# 24_to_33V__for_Ionizer_Chips.net
KiCad netlist of a schematic drawn in Altium Designer
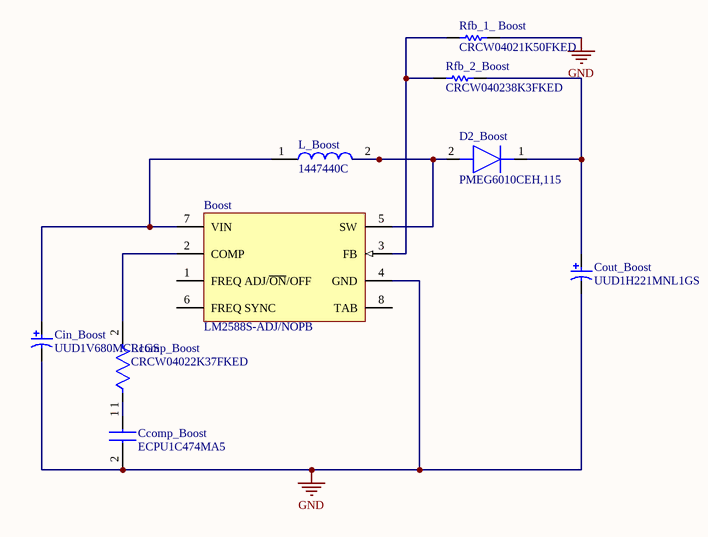
[diagram p0: 24_to_33V_(for_Ionizer_Chips).SchDoc]

(export (version "E")
  (design (tool "Eeschema 10.0.6"))
  (components
    (comp (ref "Boost")
      (value "LM2588S-ADJ/NOPB")
      (footprint "KTW0007B_N")
      (description "SIMPLE SWITCHER® 5A Flyback Regulator with Shutdown, 7-pin TO-263, Pb-Free")
      (fields (field (name "MANUFACTURER") "Texas Instruments"))
      (libsource (lib "Altium Content Vault") (part "PM-SWREG-LM2586S-12"))
    )
    (comp (ref "Ccomp_Boost")
      (value "ECPU1C474MA5")
      (footprint "SamacSys:ECPU1C154MA5")
      (description "Capacitor")
      (libsource (lib "*") (part "ECPU1C474MA5"))
    )
    (comp (ref "Cin_Boost")
      (value "UUD1V680MCL1GS")
      (footprint "NIC-CAPA2-6.3X7.7_V")
      (fields (field (name "MANUFACTURER") "Nichicon"))
      (libsource (lib "Altium Content Vault") (part "NIC-CAP-P-2"))
    )
    (comp (ref "Cout_Boost")
      (value "UUD1H221MNL1GS")
      (footprint "NIC-CAPA2-10X10_V")
      (fields (field (name "MANUFACTURER") "Nichicon"))
      (libsource (lib "Altium Content Vault") (part "NIC-CAP-P-2"))
    )
    (comp (ref "D2_Boost")
      (value "PMEG6010CEH,115")
      (footprint "SamacSys:SODFL3516X120N")
      (description "Diode")
      (fields (field (name "MOUSER PART NUMBER") "771-PMEG6010CEH-T/R"))
      (libsource (lib "*") (part "PMEG6010CEH,115"))
    )
    (comp (ref "L_Boost")
      (value "1447440C")
      (footprint "SamacSys:1447440C")
      (description "Inductor")
      (fields (field (name "MOUSER PART NUMBER") "580-1447440C"))
      (libsource (lib "*") (part "1447440C"))
    )
    (comp (ref "Rcomp_Boost")
      (value "CRCW04022K37FKED")
      (footprint "FP-CRCW0402-e3-IPC_B")
      (description "RES Thick Film, 2.37kΩ, 1%, 0.063W, 100ppm/°C, 0402")
      (fields (field (name "TOLERANCE") "1%"))
      (libsource (lib "Altium Content Vault") (part "1029c3af85768c4190bb7ad29bc67b5"))
    )
    (comp (ref "Rfb_1_ Boost")
      (value "CRCW04021K50FKED")
      (footprint "RESC1005X40X25NL05T05")
      (fields (field (name "MANUFACTURER") "Vishay Dale"))
      (libsource (lib "Altium Content Vault") (part "RES"))
    )
    (comp (ref "Rfb_2_Boost")
      (value "CRCW040238K3FKED")
      (footprint "RESC1005X40X25NL05T05")
      (fields (field (name "MANUFACTURER") "Vishay Dale"))
      (libsource (lib "Altium Content Vault") (part "RES"))
    )
  )
  (nets
    (net (code "1") (name "GND") (class "Default")
      (node (ref "Boost") (pin "4") (pinfunction "GND_4") (pintype "power_in"))
      (node (ref "Ccomp_Boost") (pin "2") (pinfunction "2_2") (pintype "passive"))
      (node (ref "Cin_Boost") (pin "2") (pinfunction "2_2") (pintype "passive"))
      (node (ref "Cout_Boost") (pin "2") (pinfunction "2_2") (pintype "passive"))
      (node (ref "Rfb_1_ Boost") (pin "2") (pinfunction "2_2") (pintype "passive"))
    )
    (net (code "2") (name "Net-(Boost-COMP)") (class "Default")
      (node (ref "Boost") (pin "2") (pinfunction "COMP_2") (pintype "passive"))
      (node (ref "Rcomp_Boost") (pin "2") (pinfunction "2_2") (pintype "passive"))
    )
    (net (code "3") (name "Net-(Boost-FB)") (class "Default")
      (node (ref "Boost") (pin "3") (pinfunction "FB_3") (pintype "input"))
      (node (ref "Rfb_1_ Boost") (pin "1") (pinfunction "1_1") (pintype "passive"))
      (node (ref "Rfb_2_Boost") (pin "1") (pinfunction "1_1") (pintype "passive"))
    )
    (net (code "4") (name "Net-(Boost-SW)") (class "Default")
      (node (ref "Boost") (pin "5") (pinfunction "SW_5") (pintype "power_in"))
      (node (ref "D2_Boost") (pin "2") (pinfunction "A_2") (pintype "passive"))
      (node (ref "L_Boost") (pin "2") (pinfunction "2_2") (pintype "passive"))
    )
    (net (code "5") (name "Net-(Boost-VIN)") (class "Default")
      (node (ref "Boost") (pin "7") (pinfunction "VIN_7") (pintype "power_in"))
      (node (ref "Cin_Boost") (pin "1") (pinfunction "1_1") (pintype "passive"))
      (node (ref "L_Boost") (pin "1") (pinfunction "1_1") (pintype "passive"))
    )
    (net (code "6") (name "Net-(Ccomp_Boost-Pad1)") (class "Default")
      (node (ref "Ccomp_Boost") (pin "1") (pinfunction "1_1") (pintype "passive"))
      (node (ref "Rcomp_Boost") (pin "1") (pinfunction "1_1") (pintype "passive"))
    )
    (net (code "7") (name "Net-(D2_Boost-K)") (class "Default")
      (node (ref "Cout_Boost") (pin "1") (pinfunction "1_1") (pintype "passive"))
      (node (ref "D2_Boost") (pin "1") (pinfunction "K_1") (pintype "passive"))
      (node (ref "Rfb_2_Boost") (pin "2") (pinfunction "2_2") (pintype "passive"))
    )
    (net (code "8") (name "unconnected-(Boost-FREQ_ADJ{slash}~{ON}{slash}OFF-Pad1)") (class "Default")
      (node (ref "Boost") (pin "1") (pinfunction "FREQ_ADJ/~{ON}/OFF_1") (pintype "passive"))
    )
    (net (code "9") (name "unconnected-(Boost-FREQ_SYNC-Pad6)") (class "Default")
      (node (ref "Boost") (pin "6") (pinfunction "FREQ_SYNC_6") (pintype "passive"))
    )
    (net (code "10") (name "unconnected-(Boost-TAB-Pad8)") (class "Default")
      (node (ref "Boost") (pin "8") (pinfunction "TAB_8") (pintype "passive"))
    )
  )
)
